# STM32_microcontroller.net
KiCad netlist of a schematic drawn in Altium Designer
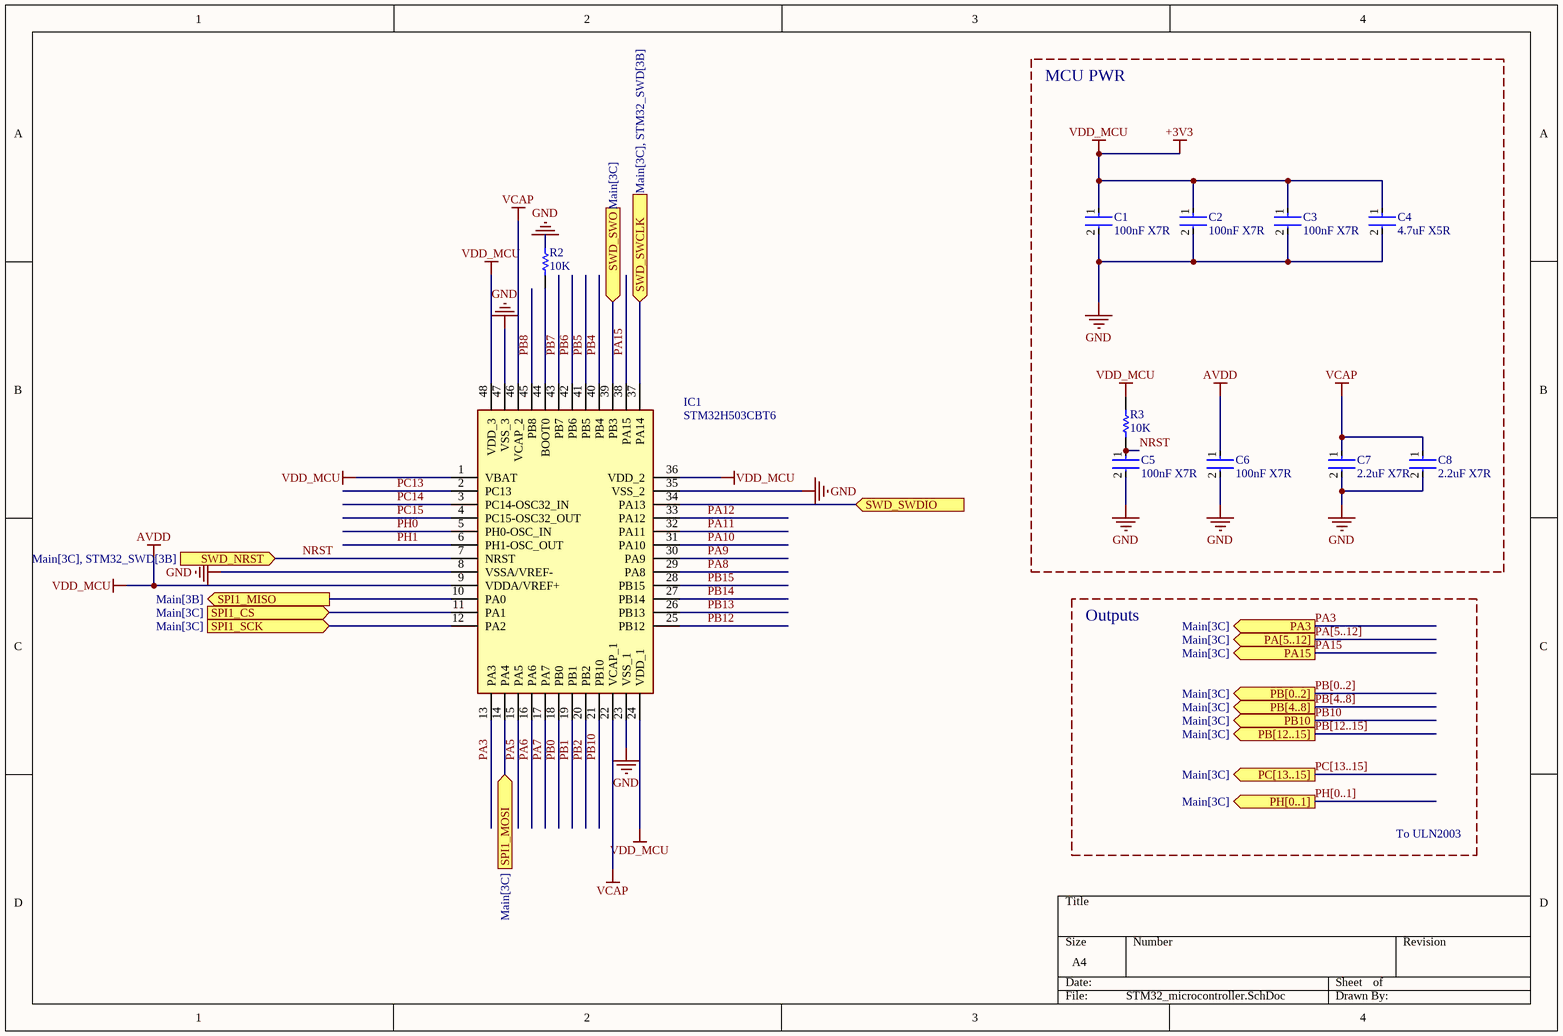
[diagram p0: STM32_microcontroller.SchDoc]

(export (version "E")
  (design (tool "Eeschema 10.0.6"))
  (components
    (comp (ref "C1")
      (value "100nF X7R")
      (footprint "FP-CL10-IPC_C")
      (description "Cap Ceramic 100nF 25V X7R ±10% Pad SMD 0603 +125°C T/R")
      (fields (field (name "TOLERANCE") "10%"))
      (libsource (lib "Altium Content Vault") (part "b4654b650e69147ec39a6b967a45e02"))
    )
    (comp (ref "C2")
      (value "100nF X7R")
      (footprint "FP-CL10-IPC_C")
      (description "Cap Ceramic 100nF 25V X7R ±10% Pad SMD 0603 +125°C T/R")
      (fields (field (name "TOLERANCE") "10%"))
      (libsource (lib "Altium Content Vault") (part "b4654b650e69147ec39a6b967a45e02"))
    )
    (comp (ref "C3")
      (value "100nF X7R")
      (footprint "FP-CL10-IPC_C")
      (description "Cap Ceramic 100nF 25V X7R ±10% Pad SMD 0603 +125°C T/R")
      (fields (field (name "TOLERANCE") "10%"))
      (libsource (lib "Altium Content Vault") (part "b4654b650e69147ec39a6b967a45e02"))
    )
    (comp (ref "C4")
      (value "4.7uF X5R")
      (footprint "FP-CL21-IPC_B")
      (description "CL21 Series 0805 4.7uF 6.3V ±10% Tolerance X5R Multilayer Ceramic Chip Capacitor")
      (fields (field (name "TOLERANCE") "10%"))
      (libsource (lib "Altium Content Vault") (part "b4654b650e69147ec39a6b967a45e02"))
    )
    (comp (ref "C5")
      (value "100nF X7R")
      (footprint "FP-CL10-IPC_C")
      (description "Cap Ceramic 100nF 25V X7R ±10% Pad SMD 0603 +125°C T/R")
      (fields (field (name "TOLERANCE") "10%"))
      (libsource (lib "Altium Content Vault") (part "b4654b650e69147ec39a6b967a45e02"))
    )
    (comp (ref "C6")
      (value "100nF X7R")
      (footprint "FP-CL10-IPC_C")
      (description "Cap Ceramic 100nF 25V X7R ±10% Pad SMD 0603 +125°C T/R")
      (fields (field (name "TOLERANCE") "10%"))
      (libsource (lib "Altium Content Vault") (part "b4654b650e69147ec39a6b967a45e02"))
    )
    (comp (ref "C7")
      (value "2.2uF X7R")
      (footprint "FP-CC0805-0_85-MFG")
      (description "CAP CER 2.2UF 6.3V X7R 0805")
      (fields
        (field (name "TOLERANCE") "0.1")
        (field (name "OCTOPART") "https://octopart.com/cc0805kkx7r5bb225-yageo-29810442")
      )
      (libsource (lib "Altium Content Vault") (part "11868f565c42a9108669ba33697ecf6"))
    )
    (comp (ref "C8")
      (value "2.2uF X7R")
      (footprint "FP-CC0805-0_85-MFG")
      (description "CAP CER 2.2UF 6.3V X7R 0805")
      (fields
        (field (name "TOLERANCE") "0.1")
        (field (name "OCTOPART") "https://octopart.com/cc0805kkx7r5bb225-yageo-29810442")
      )
      (libsource (lib "Altium Content Vault") (part "11868f565c42a9108669ba33697ecf6"))
    )
    (comp (ref "IC1")
      (value "STM32H503CBT6")
      (footprint "SamacSys:QFP50P900X900X160-48N")
      (description "Integrated Circuit")
      (fields (field (name "MOUSER PART NUMBER") "511-STM32H503CBT6"))
      (libsource (lib "*") (part "STM32H503CBT6"))
    )
    (comp (ref "R2")
      (value "10K")
      (footprint "RESC1609X50X30ML10T20")
      (fields (field (name "MANUFACTURER") "Vishay Dale") (field (name "PART NUMBER") "CRCW060310K0FKTB"))
      (libsource (lib "Altium Content Vault") (part "RES"))
    )
    (comp (ref "R3")
      (value "10K")
      (footprint "RESC1609X50X30ML10T20")
      (fields (field (name "MANUFACTURER") "Vishay Dale") (field (name "PART NUMBER") "CRCW060310K0FKTB"))
      (libsource (lib "Altium Content Vault") (part "RES"))
    )
  )
  (nets
    (net (code "1") (name "+3V3") (class "Default")
      (node (ref "C1") (pin "1") (pinfunction "1_1") (pintype "passive"))
      (node (ref "C2") (pin "1") (pinfunction "1_1") (pintype "passive"))
      (node (ref "C3") (pin "1") (pinfunction "1_1") (pintype "passive"))
      (node (ref "C4") (pin "1") (pinfunction "1_1") (pintype "passive"))
      (node (ref "C6") (pin "1") (pinfunction "1_1") (pintype "passive"))
      (node (ref "IC1") (pin "1") (pinfunction "VBAT_1") (pintype "passive"))
      (node (ref "IC1") (pin "24") (pinfunction "VDD_1_24") (pintype "passive"))
      (node (ref "IC1") (pin "36") (pinfunction "VDD_2_36") (pintype "passive"))
      (node (ref "IC1") (pin "48") (pinfunction "VDD_3_48") (pintype "passive"))
      (node (ref "IC1") (pin "9") (pinfunction "VDDA/VREF+_9") (pintype "passive"))
      (node (ref "R3") (pin "2") (pinfunction "2_2") (pintype "passive"))
    )
    (net (code "2") (name "/NRST") (class "Default")
      (node (ref "C5") (pin "1") (pinfunction "1_1") (pintype "passive"))
      (node (ref "IC1") (pin "7") (pinfunction "NRST_7") (pintype "passive"))
      (node (ref "R3") (pin "1") (pinfunction "1_1") (pintype "passive"))
    )
    (net (code "3") (name "/PA3") (class "Default")
      (node (ref "IC1") (pin "13") (pinfunction "PA3_13") (pintype "passive"))
    )
    (net (code "4") (name "/PA5") (class "Default")
      (node (ref "IC1") (pin "15") (pinfunction "PA5_15") (pintype "passive"))
    )
    (net (code "5") (name "/PA6") (class "Default")
      (node (ref "IC1") (pin "16") (pinfunction "PA6_16") (pintype "passive"))
    )
    (net (code "6") (name "/PA7") (class "Default")
      (node (ref "IC1") (pin "17") (pinfunction "PA7_17") (pintype "passive"))
    )
    (net (code "7") (name "/PA8") (class "Default")
      (node (ref "IC1") (pin "29") (pinfunction "PA8_29") (pintype "passive"))
    )
    (net (code "8") (name "/PA9") (class "Default")
      (node (ref "IC1") (pin "30") (pinfunction "PA9_30") (pintype "passive"))
    )
    (net (code "9") (name "/PA10") (class "Default")
      (node (ref "IC1") (pin "31") (pinfunction "PA10_31") (pintype "passive"))
    )
    (net (code "10") (name "/PA11") (class "Default")
      (node (ref "IC1") (pin "32") (pinfunction "PA11_32") (pintype "passive"))
    )
    (net (code "11") (name "/PA12") (class "Default")
      (node (ref "IC1") (pin "33") (pinfunction "PA12_33") (pintype "passive"))
    )
    (net (code "12") (name "/PA15") (class "Default")
      (node (ref "IC1") (pin "38") (pinfunction "PA15_38") (pintype "passive"))
    )
    (net (code "14") (name "/PB0") (class "Default")
      (node (ref "IC1") (pin "18") (pinfunction "PB0_18") (pintype "passive"))
    )
    (net (code "15") (name "/PB1") (class "Default")
      (node (ref "IC1") (pin "19") (pinfunction "PB1_19") (pintype "passive"))
    )
    (net (code "16") (name "/PB2") (class "Default")
      (node (ref "IC1") (pin "20") (pinfunction "PB2_20") (pintype "passive"))
    )
    (net (code "17") (name "/PB4") (class "Default")
      (node (ref "IC1") (pin "40") (pinfunction "PB4_40") (pintype "passive"))
    )
    (net (code "18") (name "/PB5") (class "Default")
      (node (ref "IC1") (pin "41") (pinfunction "PB5_41") (pintype "passive"))
    )
    (net (code "19") (name "/PB6") (class "Default")
      (node (ref "IC1") (pin "42") (pinfunction "PB6_42") (pintype "passive"))
    )
    (net (code "20") (name "/PB7") (class "Default")
      (node (ref "IC1") (pin "43") (pinfunction "PB7_43") (pintype "passive"))
    )
    (net (code "21") (name "/PB8") (class "Default")
      (node (ref "IC1") (pin "45") (pinfunction "PB8_45") (pintype "passive"))
    )
    (net (code "22") (name "/PB10") (class "Default")
      (node (ref "IC1") (pin "21") (pinfunction "PB10_21") (pintype "passive"))
    )
    (net (code "23") (name "/PB12") (class "Default")
      (node (ref "IC1") (pin "25") (pinfunction "PB12_25") (pintype "passive"))
    )
    (net (code "24") (name "/PB13") (class "Default")
      (node (ref "IC1") (pin "26") (pinfunction "PB13_26") (pintype "passive"))
    )
    (net (code "25") (name "/PB14") (class "Default")
      (node (ref "IC1") (pin "27") (pinfunction "PB14_27") (pintype "passive"))
    )
    (net (code "26") (name "/PB15") (class "Default")
      (node (ref "IC1") (pin "28") (pinfunction "PB15_28") (pintype "passive"))
    )
    (net (code "30") (name "/PC13") (class "Default")
      (node (ref "IC1") (pin "2") (pinfunction "PC13_2") (pintype "passive"))
    )
    (net (code "31") (name "/PC14") (class "Default")
      (node (ref "IC1") (pin "3") (pinfunction "PC14-OSC32_IN_3") (pintype "passive"))
    )
    (net (code "32") (name "/PC15") (class "Default")
      (node (ref "IC1") (pin "4") (pinfunction "PC15-OSC32_OUT_4") (pintype "passive"))
    )
    (net (code "34") (name "/PH0") (class "Default")
      (node (ref "IC1") (pin "5") (pinfunction "PH0-OSC_IN_5") (pintype "passive"))
    )
    (net (code "35") (name "/PH1") (class "Default")
      (node (ref "IC1") (pin "6") (pinfunction "PH1-OSC_OUT_6") (pintype "passive"))
    )
    (net (code "37") (name "/SPI1_CS") (class "Default")
      (node (ref "IC1") (pin "11") (pinfunction "PA1_11") (pintype "passive"))
    )
    (net (code "38") (name "/SPI1_MISO") (class "Default")
      (node (ref "IC1") (pin "10") (pinfunction "PA0_10") (pintype "passive"))
    )
    (net (code "39") (name "/SPI1_MOSI") (class "Default")
      (node (ref "IC1") (pin "14") (pinfunction "PA4_14") (pintype "passive"))
    )
    (net (code "40") (name "/SPI1_SCK") (class "Default")
      (node (ref "IC1") (pin "12") (pinfunction "PA2_12") (pintype "passive"))
    )
    (net (code "41") (name "/SWD_SWCLK") (class "Default")
      (node (ref "IC1") (pin "37") (pinfunction "PA14_37") (pintype "passive"))
    )
    (net (code "42") (name "/SWD_SWDIO") (class "Default")
      (node (ref "IC1") (pin "34") (pinfunction "PA13_34") (pintype "passive"))
    )
    (net (code "43") (name "/SWD_SWO") (class "Default")
      (node (ref "IC1") (pin "39") (pinfunction "PB3_39") (pintype "passive"))
    )
    (net (code "44") (name "GND") (class "Default")
      (node (ref "C1") (pin "2") (pinfunction "2_2") (pintype "passive"))
      (node (ref "C2") (pin "2") (pinfunction "2_2") (pintype "passive"))
      (node (ref "C3") (pin "2") (pinfunction "2_2") (pintype "passive"))
      (node (ref "C4") (pin "2") (pinfunction "2_2") (pintype "passive"))
      (node (ref "C5") (pin "2") (pinfunction "2_2") (pintype "passive"))
      (node (ref "C6") (pin "2") (pinfunction "2_2") (pintype "passive"))
      (node (ref "C7") (pin "2") (pinfunction "2_2") (pintype "passive"))
      (node (ref "C8") (pin "2") (pinfunction "2_2") (pintype "passive"))
      (node (ref "IC1") (pin "23") (pinfunction "VSS_1_23") (pintype "passive"))
      (node (ref "IC1") (pin "35") (pinfunction "VSS_2_35") (pintype "passive"))
      (node (ref "IC1") (pin "47") (pinfunction "VSS_3_47") (pintype "passive"))
      (node (ref "IC1") (pin "8") (pinfunction "VSSA/VREF-_8") (pintype "passive"))
      (node (ref "R2") (pin "2") (pinfunction "2_2") (pintype "passive"))
    )
    (net (code "45") (name "Net-(IC1-BOOT0)") (class "Default")
      (node (ref "IC1") (pin "44") (pinfunction "BOOT0_44") (pintype "passive"))
      (node (ref "R2") (pin "1") (pinfunction "1_1") (pintype "passive"))
    )
    (net (code "46") (name "VCAP") (class "Default")
      (node (ref "C7") (pin "1") (pinfunction "1_1") (pintype "passive"))
      (node (ref "C8") (pin "1") (pinfunction "1_1") (pintype "passive"))
      (node (ref "IC1") (pin "22") (pinfunction "VCAP_1_22") (pintype "passive"))
      (node (ref "IC1") (pin "46") (pinfunction "VCAP_2_46") (pintype "passive"))
    )
  )
)
